# Reaccion_UserInterface.net
KiCad netlist of a schematic drawn in EAGLE
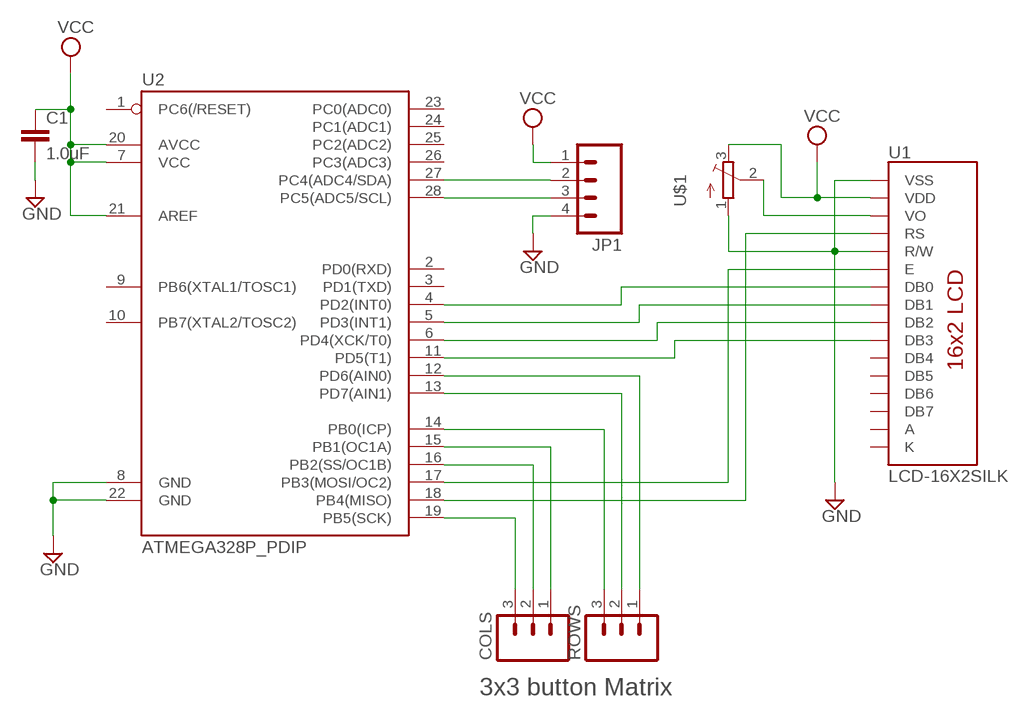
[diagram p0: schematic, sheet 1]

(export (version "E")
  (design (tool "Eeschema 10.0.6"))
  (components
    (comp (ref "C1")
      (value "1.0uF")
      (footprint "eagle-import:0805")
      (libsource (lib "eagle-import") (part "1.0UF-25V-+80/-20(0805)"))
    )
    (comp (ref "COLS")
      (value "M03")
      (footprint "eagle-import:JST-3-SMD")
      (libsource (lib "eagle-import") (part "M03"))
    )
    (comp (ref "JP1")
      (value "M04PTH")
      (footprint "eagle-import:1X04")
      (libsource (lib "eagle-import") (part "M04PTH"))
    )
    (comp (ref "ROWS")
      (value "M03")
      (footprint "eagle-import:JST-3-SMD")
      (libsource (lib "eagle-import") (part "M03"))
    )
    (comp (ref "U$1")
      (value "TRIMPOTTC33X")
      (footprint "eagle-import:TC33X")
      (libsource (lib "eagle-import") (part "TRIMPOTTC33X"))
    )
    (comp (ref "U1")
      (value "LCD-16X2SILK")
      (footprint "eagle-import:LCD-16X2")
      (libsource (lib "eagle-import") (part "LCD-16X2SILK"))
    )
    (comp (ref "U2")
      (value "ATMEGA328P_PDIP")
      (footprint "eagle-import:DIL28-3")
      (libsource (lib "eagle-import") (part "ATMEGA328P_PDIP"))
    )
  )
  (nets
    (net (code "1") (name "/A") (class "Default")
      (node (ref "U1") (pin "15") (pinfunction "A_15") (pintype "power_in"))
    )
    (net (code "2") (name "/K") (class "Default")
      (node (ref "U1") (pin "16") (pinfunction "K_16") (pintype "power_in"))
    )
    (net (code "3") (name "GND") (class "Default")
      (node (ref "C1") (pin "2") (pinfunction "2_2") (pintype "passive"))
      (node (ref "JP1") (pin "4") (pinfunction "4_4") (pintype "passive"))
      (node (ref "U$1") (pin "1") (pinfunction "A_1") (pintype "passive"))
      (node (ref "U1") (pin "1") (pinfunction "VSS_1") (pintype "power_in"))
      (node (ref "U1") (pin "5") (pinfunction "R/W_5") (pintype "input"))
      (node (ref "U2") (pin "22") (pinfunction "GND_22") (pintype "bidirectional"))
      (node (ref "U2") (pin "8") (pinfunction "GND_8") (pintype "bidirectional"))
    )
    (net (code "4") (name "Net-(U$1-S)") (class "Default")
      (node (ref "U$1") (pin "2") (pinfunction "S_2") (pintype "passive"))
      (node (ref "U1") (pin "3") (pinfunction "VO_3") (pintype "bidirectional"))
    )
    (net (code "5") (name "Net-(U1-DB0)") (class "Default")
      (node (ref "U1") (pin "7") (pinfunction "DB0_7") (pintype "bidirectional"))
      (node (ref "U2") (pin "4") (pinfunction "PD2(INT0)_4") (pintype "bidirectional"))
    )
    (net (code "6") (name "Net-(U1-DB1)") (class "Default")
      (node (ref "U1") (pin "8") (pinfunction "DB1_8") (pintype "bidirectional"))
      (node (ref "U2") (pin "5") (pinfunction "PD3(INT1)_5") (pintype "bidirectional"))
    )
    (net (code "7") (name "Net-(U1-DB2)") (class "Default")
      (node (ref "U1") (pin "9") (pinfunction "DB2_9") (pintype "bidirectional"))
      (node (ref "U2") (pin "6") (pinfunction "PD4(XCK/T0)_6") (pintype "bidirectional"))
    )
    (net (code "8") (name "Net-(U1-DB3)") (class "Default")
      (node (ref "U1") (pin "10") (pinfunction "DB3_10") (pintype "bidirectional"))
      (node (ref "U2") (pin "11") (pinfunction "PD5(T1)_11") (pintype "bidirectional"))
    )
    (net (code "9") (name "Net-(U1-E)") (class "Default")
      (node (ref "U1") (pin "6") (pinfunction "E_6") (pintype "input"))
      (node (ref "U2") (pin "17") (pinfunction "PB3(MOSI/OC2)_17") (pintype "bidirectional"))
    )
    (net (code "10") (name "Net-(U1-RS)") (class "Default")
      (node (ref "U1") (pin "4") (pinfunction "RS_4") (pintype "input"))
      (node (ref "U2") (pin "18") (pinfunction "PB4(MISO)_18") (pintype "bidirectional"))
    )
    (net (code "11") (name "Net-(U2-PB0(ICP))") (class "Default")
      (node (ref "ROWS") (pin "3") (pinfunction "3_3") (pintype "passive"))
      (node (ref "U2") (pin "14") (pinfunction "PB0(ICP)_14") (pintype "bidirectional"))
    )
    (net (code "12") (name "Net-(U2-PB1(OC1A))") (class "Default")
      (node (ref "COLS") (pin "1") (pinfunction "1_1") (pintype "passive"))
      (node (ref "U2") (pin "15") (pinfunction "PB1(OC1A)_15") (pintype "bidirectional"))
    )
    (net (code "13") (name "Net-(U2-PB2(SS{slash}OC1B))") (class "Default")
      (node (ref "COLS") (pin "2") (pinfunction "2_2") (pintype "passive"))
      (node (ref "U2") (pin "16") (pinfunction "PB2(SS/OC1B)_16") (pintype "bidirectional"))
    )
    (net (code "14") (name "Net-(U2-PB5(SCK))") (class "Default")
      (node (ref "COLS") (pin "3") (pinfunction "3_3") (pintype "passive"))
      (node (ref "U2") (pin "19") (pinfunction "PB5(SCK)_19") (pintype "bidirectional"))
    )
    (net (code "15") (name "Net-(U2-PC4(ADC4{slash}SDA))") (class "Default")
      (node (ref "JP1") (pin "2") (pinfunction "2_2") (pintype "passive"))
      (node (ref "U2") (pin "27") (pinfunction "PC4(ADC4/SDA)_27") (pintype "bidirectional"))
    )
    (net (code "16") (name "Net-(U2-PC5(ADC5{slash}SCL))") (class "Default")
      (node (ref "JP1") (pin "3") (pinfunction "3_3") (pintype "passive"))
      (node (ref "U2") (pin "28") (pinfunction "PC5(ADC5/SCL)_28") (pintype "bidirectional"))
    )
    (net (code "17") (name "Net-(U2-PD6(AIN0))") (class "Default")
      (node (ref "ROWS") (pin "1") (pinfunction "1_1") (pintype "passive"))
      (node (ref "U2") (pin "12") (pinfunction "PD6(AIN0)_12") (pintype "bidirectional"))
    )
    (net (code "18") (name "Net-(U2-PD7(AIN1))") (class "Default")
      (node (ref "ROWS") (pin "2") (pinfunction "2_2") (pintype "passive"))
      (node (ref "U2") (pin "13") (pinfunction "PD7(AIN1)_13") (pintype "bidirectional"))
    )
    (net (code "19") (name "VCC") (class "Default")
      (node (ref "C1") (pin "1") (pinfunction "1_1") (pintype "passive"))
      (node (ref "JP1") (pin "1") (pinfunction "1_1") (pintype "passive"))
      (node (ref "U$1") (pin "3") (pinfunction "E_3") (pintype "passive"))
      (node (ref "U1") (pin "2") (pinfunction "VDD_2") (pintype "power_in"))
      (node (ref "U2") (pin "20") (pinfunction "AVCC_20") (pintype "bidirectional"))
      (node (ref "U2") (pin "21") (pinfunction "AREF_21") (pintype "bidirectional"))
      (node (ref "U2") (pin "7") (pinfunction "VCC_7") (pintype "bidirectional"))
    )
    (net (code "20") (name "unconnected-(U1-DB4-Pad11)") (class "Default")
      (node (ref "U1") (pin "11") (pinfunction "DB4_11") (pintype "bidirectional"))
    )
    (net (code "21") (name "unconnected-(U1-DB5-Pad12)") (class "Default")
      (node (ref "U1") (pin "12") (pinfunction "DB5_12") (pintype "bidirectional"))
    )
    (net (code "22") (name "unconnected-(U1-DB6-Pad13)") (class "Default")
      (node (ref "U1") (pin "13") (pinfunction "DB6_13") (pintype "bidirectional"))
    )
    (net (code "23") (name "unconnected-(U1-DB7-Pad14)") (class "Default")
      (node (ref "U1") (pin "14") (pinfunction "DB7_14") (pintype "bidirectional"))
    )
    (net (code "24") (name "unconnected-(U2-PB6(XTAL1{slash}TOSC1)-Pad9)") (class "Default")
      (node (ref "U2") (pin "9") (pinfunction "PB6(XTAL1/TOSC1)_9") (pintype "bidirectional"))
    )
    (net (code "25") (name "unconnected-(U2-PB7(XTAL2{slash}TOSC2)-Pad10)") (class "Default")
      (node (ref "U2") (pin "10") (pinfunction "PB7(XTAL2/TOSC2)_10") (pintype "bidirectional"))
    )
    (net (code "26") (name "unconnected-(U2-PC0(ADC0)-Pad23)") (class "Default")
      (node (ref "U2") (pin "23") (pinfunction "PC0(ADC0)_23") (pintype "bidirectional"))
    )
    (net (code "27") (name "unconnected-(U2-PC1(ADC1)-Pad24)") (class "Default")
      (node (ref "U2") (pin "24") (pinfunction "PC1(ADC1)_24") (pintype "bidirectional"))
    )
    (net (code "28") (name "unconnected-(U2-PC2(ADC2)-Pad25)") (class "Default")
      (node (ref "U2") (pin "25") (pinfunction "PC2(ADC2)_25") (pintype "bidirectional"))
    )
    (net (code "29") (name "unconnected-(U2-PC3(ADC3)-Pad26)") (class "Default")
      (node (ref "U2") (pin "26") (pinfunction "PC3(ADC3)_26") (pintype "bidirectional"))
    )
    (net (code "30") (name "unconnected-(U2-PC6({slash}RESET)-Pad1)") (class "Default")
      (node (ref "U2") (pin "1") (pinfunction "PC6(/RESET)_1") (pintype "bidirectional"))
    )
    (net (code "31") (name "unconnected-(U2-PD0(RXD)-Pad2)") (class "Default")
      (node (ref "U2") (pin "2") (pinfunction "PD0(RXD)_2") (pintype "bidirectional"))
    )
    (net (code "32") (name "unconnected-(U2-PD1(TXD)-Pad3)") (class "Default")
      (node (ref "U2") (pin "3") (pinfunction "PD1(TXD)_3") (pintype "bidirectional"))
    )
  )
)
